# CAN.net
KiCad netlist of a schematic drawn in Altium Designer
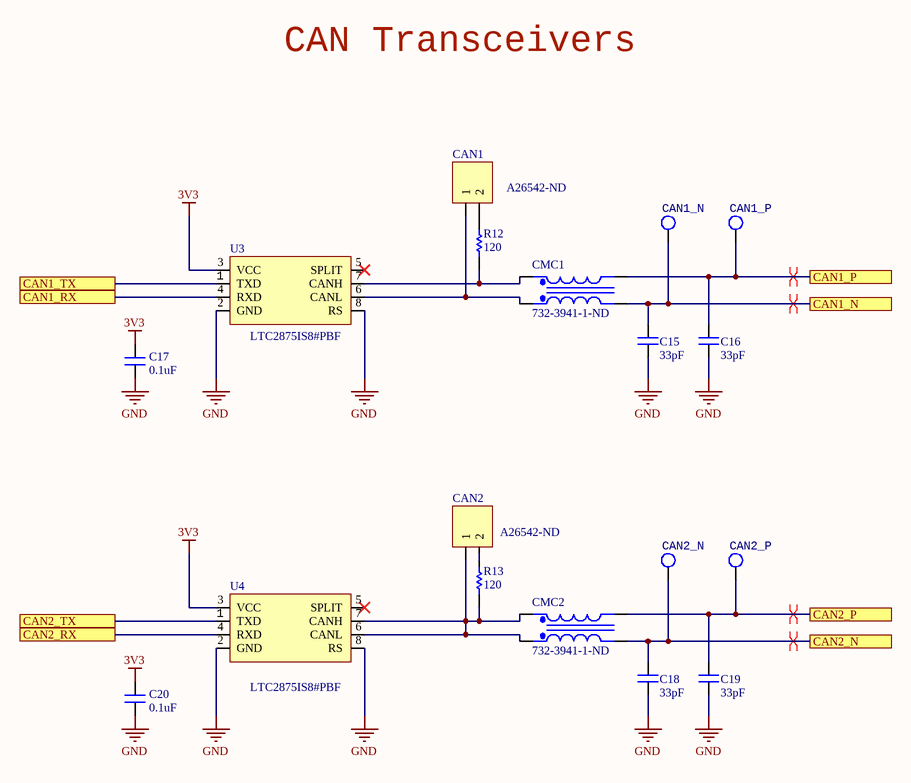
[diagram p0: CAN.SchDoc]

(export (version "E")
  (design (tool "Eeschema 10.0.6"))
  (components
    (comp (ref "C15")
      (value "CAP_33pF_50V_0603")
      (footprint "CAPC0603(1608)55_N")
      (description "CAP CER 33PF 50V C0G/NP0")
      (fields
        (field (name "VOLTAGE") "50V")
        (field (name "TOLERANCE") "5%")
        (field (name "CAPACITANCE") "33pF")
      )
      (libsource (lib "UWRT_Schematic_Library_2020") (part "CAP_33pF_50V_0603"))
    )
    (comp (ref "C16")
      (value "CAP_33pF_50V_0603")
      (footprint "CAPC0603(1608)55_N")
      (description "CAP CER 33PF 50V C0G/NP0")
      (fields
        (field (name "VOLTAGE") "50V")
        (field (name "TOLERANCE") "5%")
        (field (name "CAPACITANCE") "33pF")
      )
      (libsource (lib "UWRT_Schematic_Library_2020") (part "CAP_33pF_50V_0603"))
    )
    (comp (ref "C17")
      (value "0.1uF")
      (footprint "CAPC0603(1608)55_N")
      (description "CAP CER 0.1UF 16V X7R 0603")
      (fields (field (name "Comment") "CAP_0.1uF_16V_0603"))
      (libsource (lib "UWRT_Schematic_Library_2020") (part "CAP_0.1uF_16V_0603"))
    )
    (comp (ref "C18")
      (value "CAP_33pF_50V_0603")
      (footprint "CAPC0603(1608)55_N")
      (description "CAP CER 33PF 50V C0G/NP0")
      (fields
        (field (name "VOLTAGE") "50V")
        (field (name "TOLERANCE") "5%")
        (field (name "CAPACITANCE") "33pF")
      )
      (libsource (lib "UWRT_Schematic_Library_2020") (part "CAP_33pF_50V_0603"))
    )
    (comp (ref "C19")
      (value "CAP_33pF_50V_0603")
      (footprint "CAPC0603(1608)55_N")
      (description "CAP CER 33PF 50V C0G/NP0")
      (fields
        (field (name "VOLTAGE") "50V")
        (field (name "TOLERANCE") "5%")
        (field (name "CAPACITANCE") "33pF")
      )
      (libsource (lib "UWRT_Schematic_Library_2020") (part "CAP_33pF_50V_0603"))
    )
    (comp (ref "C20")
      (value "0.1uF")
      (footprint "CAPC0603(1608)55_N")
      (description "CAP CER 0.1UF 16V X7R 0603")
      (fields (field (name "Comment") "CAP_0.1uF_16V_0603"))
      (libsource (lib "UWRT_Schematic_Library_2020") (part "CAP_0.1uF_16V_0603"))
    )
    (comp (ref "CAN1")
      (value "JUMPER_2")
      (footprint "HDR1X2")
      (description "HEADER 2X1")
      (fields (field (name "SUPPLIER PART NUMBER 1") "A26542-ND"))
      (libsource (lib "UWRT_Schematic_Library_2020") (part "JUMPER_2"))
    )
    (comp (ref "CAN1_N")
      (value "TESTPOINT_LOOP")
      (footprint "TESTPOINT_LOOP")
      (description "Loop testpoint through-hole pad")
      (libsource (lib "UWRT_Schematic_Library_2020") (part "TESTPOINT_LOOP"))
    )
    (comp (ref "CAN1_P")
      (value "TESTPOINT_LOOP")
      (footprint "TESTPOINT_LOOP")
      (description "Loop testpoint through-hole pad")
      (libsource (lib "UWRT_Schematic_Library_2020") (part "TESTPOINT_LOOP"))
    )
    (comp (ref "CAN2")
      (value "JUMPER_2")
      (footprint "HDR1X2")
      (description "HEADER 2X1")
      (fields (field (name "SUPPLIER PART NUMBER 1") "A26542-ND"))
      (libsource (lib "UWRT_Schematic_Library_2020") (part "JUMPER_2"))
    )
    (comp (ref "CAN2_N")
      (value "TESTPOINT_LOOP")
      (footprint "TESTPOINT_LOOP")
      (description "Loop testpoint through-hole pad")
      (libsource (lib "UWRT_Schematic_Library_2020") (part "TESTPOINT_LOOP"))
    )
    (comp (ref "CAN2_P")
      (value "TESTPOINT_LOOP")
      (footprint "TESTPOINT_LOOP")
      (description "Loop testpoint through-hole pad")
      (libsource (lib "UWRT_Schematic_Library_2020") (part "TESTPOINT_LOOP"))
    )
    (comp (ref "CMC1")
      (value "CMC_51uH")
      (footprint "744212510")
      (description "CMC 51uH 300MA 2LN SMD")
      (fields (field (name "TOLERANCE") "50%") (field (name "SUPPLIER PART NUMBER 1") "732-3941-1-ND"))
      (libsource (lib "UWRT_Schematic_Library_2020") (part "CMC_51uH"))
    )
    (comp (ref "CMC2")
      (value "CMC_51uH")
      (footprint "744212510")
      (description "CMC 51uH 300MA 2LN SMD")
      (fields (field (name "TOLERANCE") "50%") (field (name "SUPPLIER PART NUMBER 1") "732-3941-1-ND"))
      (libsource (lib "UWRT_Schematic_Library_2020") (part "CMC_51uH"))
    )
    (comp (ref "R12")
      (value "120")
      (footprint "RESC0603(1608)_N")
      (description "RES SMD 120 OHM 5% 1/10W 0603")
      (fields (field (name "TOLERANCE") "5%") (field (name "Comment") "RES_120R_0603"))
      (libsource (lib "UWRT_Schematic_Library_2020") (part "RES_120R_0603"))
    )
    (comp (ref "R13")
      (value "120")
      (footprint "RESC0603(1608)_N")
      (description "RES SMD 120 OHM 5% 1/10W 0603")
      (fields (field (name "TOLERANCE") "5%") (field (name "Comment") "RES_120R_0603"))
      (libsource (lib "UWRT_Schematic_Library_2020") (part "RES_120R_0603"))
    )
    (comp (ref "U3")
      (value "IC TXRX CAN")
      (footprint "LT-S8_N")
      (description "IC TXRX CAN 4MBPS 8SO")
      (fields (field (name "MANUFACTURER PART NUMBER 1") "LTC2875IS8#PBF"))
      (libsource (lib "UWRT_Schematic_Library_2020") (part "LTC2875"))
    )
    (comp (ref "U4")
      (value "IC TXRX CAN")
      (footprint "LT-S8_N")
      (description "IC TXRX CAN 4MBPS 8SO")
      (fields (field (name "MANUFACTURER PART NUMBER 1") "LTC2875IS8#PBF"))
      (libsource (lib "UWRT_Schematic_Library_2020") (part "LTC2875"))
    )
  )
  (nets
    (net (code "1") (name "/CAN1_N") (class "Default")
      (node (ref "C15") (pin "2") (pinfunction "2_2") (pintype "passive"))
      (node (ref "CAN1_N") (pin "1") (pintype "passive"))
      (node (ref "CMC1") (pin "5") (pinfunction "Pri-_5") (pintype "passive"))
    )
    (net (code "2") (name "/CAN1_P") (class "Default")
      (node (ref "C16") (pin "2") (pinfunction "2_2") (pintype "passive"))
      (node (ref "CAN1_P") (pin "1") (pintype "passive"))
      (node (ref "CMC1") (pin "4") (pinfunction "Sec-_4") (pintype "passive"))
    )
    (net (code "3") (name "/CAN1_RX") (class "Default")
      (node (ref "U3") (pin "4") (pinfunction "RXD_4") (pintype "passive"))
    )
    (net (code "4") (name "/CAN1_TX") (class "Default")
      (node (ref "U3") (pin "1") (pinfunction "TXD_1") (pintype "passive"))
    )
    (net (code "5") (name "/CAN2_N") (class "Default")
      (node (ref "C18") (pin "2") (pinfunction "2_2") (pintype "passive"))
      (node (ref "CAN2_N") (pin "1") (pintype "passive"))
      (node (ref "CMC2") (pin "5") (pinfunction "Pri-_5") (pintype "passive"))
    )
    (net (code "6") (name "/CAN2_P") (class "Default")
      (node (ref "C19") (pin "2") (pinfunction "2_2") (pintype "passive"))
      (node (ref "CAN2_P") (pin "1") (pintype "passive"))
      (node (ref "CMC2") (pin "4") (pinfunction "Sec-_4") (pintype "passive"))
    )
    (net (code "7") (name "/CAN2_RX") (class "Default")
      (node (ref "U4") (pin "4") (pinfunction "RXD_4") (pintype "passive"))
    )
    (net (code "8") (name "/CAN2_TX") (class "Default")
      (node (ref "U4") (pin "1") (pinfunction "TXD_1") (pintype "passive"))
    )
    (net (code "9") (name "3V3") (class "Default")
      (node (ref "C17") (pin "1") (pinfunction "1_1") (pintype "passive"))
      (node (ref "C20") (pin "1") (pinfunction "1_1") (pintype "passive"))
      (node (ref "U3") (pin "3") (pinfunction "VCC_3") (pintype "passive"))
      (node (ref "U4") (pin "3") (pinfunction "VCC_3") (pintype "passive"))
    )
    (net (code "10") (name "GND") (class "Default")
      (node (ref "C15") (pin "1") (pinfunction "1_1") (pintype "passive"))
      (node (ref "C16") (pin "1") (pinfunction "1_1") (pintype "passive"))
      (node (ref "C17") (pin "2") (pinfunction "2_2") (pintype "passive"))
      (node (ref "C18") (pin "1") (pinfunction "1_1") (pintype "passive"))
      (node (ref "C19") (pin "1") (pinfunction "1_1") (pintype "passive"))
      (node (ref "C20") (pin "2") (pinfunction "2_2") (pintype "passive"))
      (node (ref "U3") (pin "2") (pinfunction "GND_2") (pintype "passive"))
      (node (ref "U3") (pin "8") (pinfunction "RS_8") (pintype "passive"))
      (node (ref "U4") (pin "2") (pinfunction "GND_2") (pintype "passive"))
      (node (ref "U4") (pin "8") (pinfunction "RS_8") (pintype "passive"))
    )
    (net (code "11") (name "Net-(CAN1-Pad2)") (class "Default")
      (node (ref "CAN1") (pin "2") (pinfunction "2_2") (pintype "passive"))
      (node (ref "R12") (pin "1") (pinfunction "1_1") (pintype "passive"))
    )
    (net (code "12") (name "Net-(CAN2-Pad2)") (class "Default")
      (node (ref "CAN2") (pin "2") (pinfunction "2_2") (pintype "passive"))
      (node (ref "R13") (pin "1") (pinfunction "1_1") (pintype "passive"))
    )
    (net (code "13") (name "Net-(CMC1-Pri+)") (class "Default")
      (node (ref "CAN1") (pin "1") (pinfunction "1_1") (pintype "passive"))
      (node (ref "CMC1") (pin "1") (pinfunction "Pri+_1") (pintype "passive"))
      (node (ref "U3") (pin "6") (pinfunction "CANL_6") (pintype "passive"))
    )
    (net (code "14") (name "Net-(CMC1-Sec+)") (class "Default")
      (node (ref "CMC1") (pin "3") (pinfunction "Sec+_3") (pintype "passive"))
      (node (ref "R12") (pin "2") (pinfunction "2_2") (pintype "passive"))
      (node (ref "U3") (pin "7") (pinfunction "CANH_7") (pintype "passive"))
    )
    (net (code "15") (name "Net-(CMC2-Pri+)") (class "Default")
      (node (ref "CAN2") (pin "1") (pinfunction "1_1") (pintype "passive"))
      (node (ref "CMC2") (pin "1") (pinfunction "Pri+_1") (pintype "passive"))
      (node (ref "CMC2") (pin "3") (pinfunction "Sec+_3") (pintype "passive"))
      (node (ref "R13") (pin "2") (pinfunction "2_2") (pintype "passive"))
      (node (ref "U4") (pin "6") (pinfunction "CANL_6") (pintype "passive"))
      (node (ref "U4") (pin "7") (pinfunction "CANH_7") (pintype "passive"))
    )
    (net (code "16") (name "unconnected-(U3-SPLIT-Pad5)") (class "Default")
      (node (ref "U3") (pin "5") (pinfunction "SPLIT_5") (pintype "passive+no_connect"))
    )
    (net (code "17") (name "unconnected-(U4-SPLIT-Pad5)") (class "Default")
      (node (ref "U4") (pin "5") (pinfunction "SPLIT_5") (pintype "passive+no_connect"))
    )
  )
)
